# EthernetBoardPanel.net
KiCad netlist of a schematic drawn in EAGLE
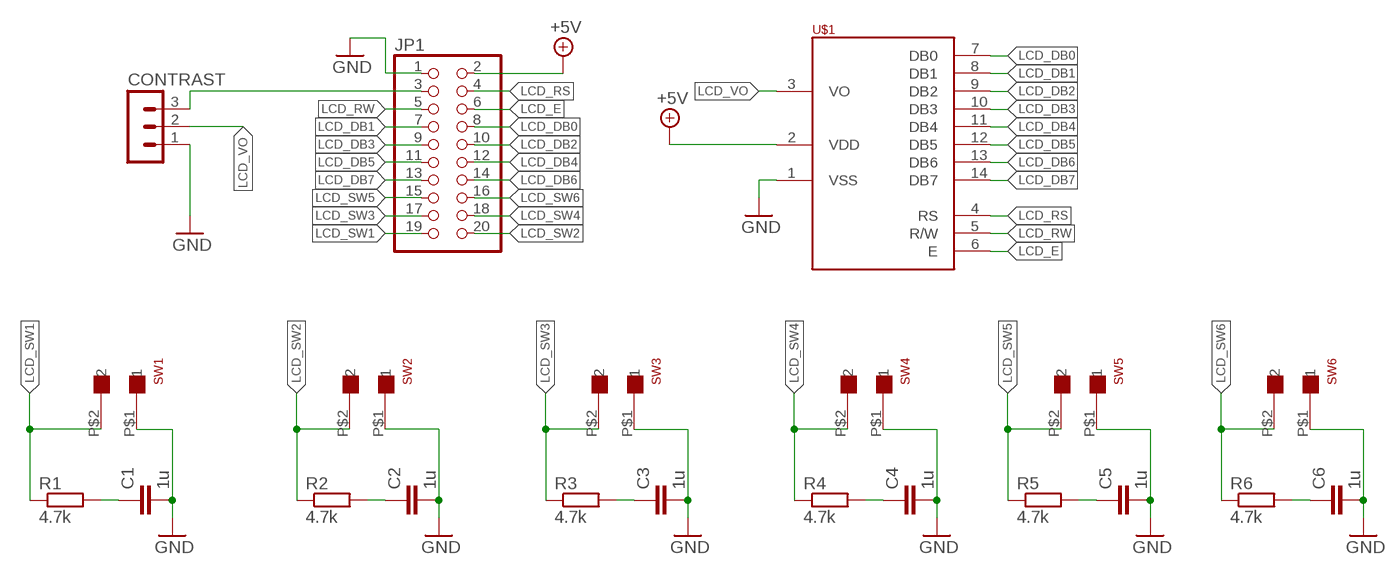
[diagram p0: schematic, sheet 1]

(export (version "E")
  (design (tool "Eeschema 10.0.6"))
  (components
    (comp (ref "C1")
      (value "1u")
      (footprint "eagle-import:C025-025X050")
      (libsource (lib "eagle-import") (part "C-EU025-025X050"))
    )
    (comp (ref "C2")
      (value "1u")
      (footprint "eagle-import:C025-025X050")
      (libsource (lib "eagle-import") (part "C-EU025-025X050"))
    )
    (comp (ref "C3")
      (value "1u")
      (footprint "eagle-import:C025-025X050")
      (libsource (lib "eagle-import") (part "C-EU025-025X050"))
    )
    (comp (ref "C4")
      (value "1u")
      (footprint "eagle-import:C025-025X050")
      (libsource (lib "eagle-import") (part "C-EU025-025X050"))
    )
    (comp (ref "C5")
      (value "1u")
      (footprint "eagle-import:C025-025X050")
      (libsource (lib "eagle-import") (part "C-EU025-025X050"))
    )
    (comp (ref "C6")
      (value "1u")
      (footprint "eagle-import:C025-025X050")
      (libsource (lib "eagle-import") (part "C-EU025-025X050"))
    )
    (comp (ref "CONTRAST")
      (value "MA03-1")
      (footprint "eagle-import:MA03-1")
      (libsource (lib "eagle-import") (part "MA03-1"))
    )
    (comp (ref "JP1")
      (value "PINHD-2X10")
      (footprint "eagle-import:2X10")
      (libsource (lib "eagle-import") (part "PINHD-2X10"))
    )
    (comp (ref "R1")
      (value "4.7k")
      (footprint "eagle-import:0204_7")
      (libsource (lib "eagle-import") (part "R-EU_0204/7"))
    )
    (comp (ref "R2")
      (value "4.7k")
      (footprint "eagle-import:0204_7")
      (libsource (lib "eagle-import") (part "R-EU_0204/7"))
    )
    (comp (ref "R3")
      (value "4.7k")
      (footprint "eagle-import:0204_7")
      (libsource (lib "eagle-import") (part "R-EU_0204/7"))
    )
    (comp (ref "R4")
      (value "4.7k")
      (footprint "eagle-import:0204_7")
      (libsource (lib "eagle-import") (part "R-EU_0204/7"))
    )
    (comp (ref "R5")
      (value "4.7k")
      (footprint "eagle-import:0204_7")
      (libsource (lib "eagle-import") (part "R-EU_0204/7"))
    )
    (comp (ref "R6")
      (value "4.7k")
      (footprint "eagle-import:0204_7")
      (libsource (lib "eagle-import") (part "R-EU_0204/7"))
    )
    (comp (ref "SW1")
      (value "XH-2")
      (footprint "eagle-import:XH-2")
      (libsource (lib "eagle-import") (part "XH-2"))
    )
    (comp (ref "SW2")
      (value "XH-2")
      (footprint "eagle-import:XH-2")
      (libsource (lib "eagle-import") (part "XH-2"))
    )
    (comp (ref "SW3")
      (value "XH-2")
      (footprint "eagle-import:XH-2")
      (libsource (lib "eagle-import") (part "XH-2"))
    )
    (comp (ref "SW4")
      (value "XH-2")
      (footprint "eagle-import:XH-2")
      (libsource (lib "eagle-import") (part "XH-2"))
    )
    (comp (ref "SW5")
      (value "XH-2")
      (footprint "eagle-import:XH-2")
      (libsource (lib "eagle-import") (part "XH-2"))
    )
    (comp (ref "SW6")
      (value "XH-2")
      (footprint "eagle-import:XH-2")
      (libsource (lib "eagle-import") (part "XH-2"))
    )
    (comp (ref "U$1")
      (value "SC2004")
      (footprint "eagle-import:SC2004")
      (libsource (lib "eagle-import") (part "SC2004"))
    )
  )
  (nets
    (net (code "1") (name "+5V") (class "Default")
      (node (ref "JP1") (pin "2") (pinfunction "2_2") (pintype "passive"))
      (node (ref "U$1") (pin "2") (pinfunction "VDD_2") (pintype "power_in"))
    )
    (net (code "2") (name "GND") (class "Default")
      (node (ref "C1") (pin "2") (pinfunction "2_2") (pintype "passive"))
      (node (ref "C2") (pin "2") (pinfunction "2_2") (pintype "passive"))
      (node (ref "C3") (pin "2") (pinfunction "2_2") (pintype "passive"))
      (node (ref "C4") (pin "2") (pinfunction "2_2") (pintype "passive"))
      (node (ref "C5") (pin "2") (pinfunction "2_2") (pintype "passive"))
      (node (ref "C6") (pin "2") (pinfunction "2_2") (pintype "passive"))
      (node (ref "CONTRAST") (pin "1") (pinfunction "1_1") (pintype "passive"))
      (node (ref "JP1") (pin "1") (pinfunction "1_1") (pintype "passive"))
      (node (ref "SW1") (pin "P$1") (pinfunction "1_P$1") (pintype "bidirectional"))
      (node (ref "SW2") (pin "P$1") (pinfunction "1_P$1") (pintype "bidirectional"))
      (node (ref "SW3") (pin "P$1") (pinfunction "1_P$1") (pintype "bidirectional"))
      (node (ref "SW4") (pin "P$1") (pinfunction "1_P$1") (pintype "bidirectional"))
      (node (ref "SW5") (pin "P$1") (pinfunction "1_P$1") (pintype "bidirectional"))
      (node (ref "SW6") (pin "P$1") (pinfunction "1_P$1") (pintype "bidirectional"))
      (node (ref "U$1") (pin "1") (pinfunction "VSS_1") (pintype "power_in"))
    )
    (net (code "3") (name "LCD_DB0") (class "Default")
      (node (ref "JP1") (pin "8") (pinfunction "8_8") (pintype "passive"))
      (node (ref "U$1") (pin "7") (pinfunction "DB0_7") (pintype "bidirectional"))
    )
    (net (code "4") (name "LCD_DB1") (class "Default")
      (node (ref "JP1") (pin "7") (pinfunction "7_7") (pintype "passive"))
      (node (ref "U$1") (pin "8") (pinfunction "DB1_8") (pintype "bidirectional"))
    )
    (net (code "5") (name "LCD_DB2") (class "Default")
      (node (ref "JP1") (pin "10") (pinfunction "10_10") (pintype "passive"))
      (node (ref "U$1") (pin "9") (pinfunction "DB2_9") (pintype "bidirectional"))
    )
    (net (code "6") (name "LCD_DB3") (class "Default")
      (node (ref "JP1") (pin "9") (pinfunction "9_9") (pintype "passive"))
      (node (ref "U$1") (pin "10") (pinfunction "DB3_10") (pintype "bidirectional"))
    )
    (net (code "7") (name "LCD_DB4") (class "Default")
      (node (ref "JP1") (pin "12") (pinfunction "12_12") (pintype "passive"))
      (node (ref "U$1") (pin "11") (pinfunction "DB4_11") (pintype "bidirectional"))
    )
    (net (code "8") (name "LCD_DB5") (class "Default")
      (node (ref "JP1") (pin "11") (pinfunction "11_11") (pintype "passive"))
      (node (ref "U$1") (pin "12") (pinfunction "DB5_12") (pintype "bidirectional"))
    )
    (net (code "9") (name "LCD_DB6") (class "Default")
      (node (ref "JP1") (pin "14") (pinfunction "14_14") (pintype "passive"))
      (node (ref "U$1") (pin "13") (pinfunction "DB6_13") (pintype "bidirectional"))
    )
    (net (code "10") (name "LCD_DB7") (class "Default")
      (node (ref "JP1") (pin "13") (pinfunction "13_13") (pintype "passive"))
      (node (ref "U$1") (pin "14") (pinfunction "DB7_14") (pintype "bidirectional"))
    )
    (net (code "11") (name "LCD_E") (class "Default")
      (node (ref "JP1") (pin "6") (pinfunction "6_6") (pintype "passive"))
      (node (ref "U$1") (pin "6") (pinfunction "E_6") (pintype "bidirectional"))
    )
    (net (code "12") (name "LCD_RS") (class "Default")
      (node (ref "JP1") (pin "4") (pinfunction "4_4") (pintype "passive"))
      (node (ref "U$1") (pin "4") (pinfunction "RS_4") (pintype "bidirectional"))
    )
    (net (code "13") (name "LCD_RW") (class "Default")
      (node (ref "JP1") (pin "5") (pinfunction "5_5") (pintype "passive"))
      (node (ref "U$1") (pin "5") (pinfunction "R/W_5") (pintype "bidirectional"))
    )
    (net (code "14") (name "LCD_SW1") (class "Default")
      (node (ref "JP1") (pin "19") (pinfunction "19_19") (pintype "passive"))
      (node (ref "R1") (pin "1") (pinfunction "1_1") (pintype "passive"))
      (node (ref "SW1") (pin "P$2") (pinfunction "2_P$2") (pintype "bidirectional"))
    )
    (net (code "15") (name "LCD_SW2") (class "Default")
      (node (ref "JP1") (pin "20") (pinfunction "20_20") (pintype "passive"))
      (node (ref "R2") (pin "1") (pinfunction "1_1") (pintype "passive"))
      (node (ref "SW2") (pin "P$2") (pinfunction "2_P$2") (pintype "bidirectional"))
    )
    (net (code "16") (name "LCD_SW3") (class "Default")
      (node (ref "JP1") (pin "17") (pinfunction "17_17") (pintype "passive"))
      (node (ref "R3") (pin "1") (pinfunction "1_1") (pintype "passive"))
      (node (ref "SW3") (pin "P$2") (pinfunction "2_P$2") (pintype "bidirectional"))
    )
    (net (code "17") (name "LCD_SW4") (class "Default")
      (node (ref "JP1") (pin "18") (pinfunction "18_18") (pintype "passive"))
      (node (ref "R4") (pin "1") (pinfunction "1_1") (pintype "passive"))
      (node (ref "SW4") (pin "P$2") (pinfunction "2_P$2") (pintype "bidirectional"))
    )
    (net (code "18") (name "LCD_SW5") (class "Default")
      (node (ref "JP1") (pin "15") (pinfunction "15_15") (pintype "passive"))
      (node (ref "R5") (pin "1") (pinfunction "1_1") (pintype "passive"))
      (node (ref "SW5") (pin "P$2") (pinfunction "2_P$2") (pintype "bidirectional"))
    )
    (net (code "19") (name "LCD_SW6") (class "Default")
      (node (ref "JP1") (pin "16") (pinfunction "16_16") (pintype "passive"))
      (node (ref "R6") (pin "1") (pinfunction "1_1") (pintype "passive"))
      (node (ref "SW6") (pin "P$2") (pinfunction "2_P$2") (pintype "bidirectional"))
    )
    (net (code "20") (name "LCD_VO") (class "Default")
      (node (ref "CONTRAST") (pin "2") (pinfunction "2_2") (pintype "passive"))
      (node (ref "U$1") (pin "3") (pinfunction "VO_3") (pintype "bidirectional"))
    )
    (net (code "21") (name "Net-(C1-Pad1)") (class "Default")
      (node (ref "C1") (pin "1") (pinfunction "1_1") (pintype "passive"))
      (node (ref "R1") (pin "2") (pinfunction "2_2") (pintype "passive"))
    )
    (net (code "22") (name "Net-(C2-Pad1)") (class "Default")
      (node (ref "C2") (pin "1") (pinfunction "1_1") (pintype "passive"))
      (node (ref "R2") (pin "2") (pinfunction "2_2") (pintype "passive"))
    )
    (net (code "23") (name "Net-(C3-Pad1)") (class "Default")
      (node (ref "C3") (pin "1") (pinfunction "1_1") (pintype "passive"))
      (node (ref "R3") (pin "2") (pinfunction "2_2") (pintype "passive"))
    )
    (net (code "24") (name "Net-(C4-Pad1)") (class "Default")
      (node (ref "C4") (pin "1") (pinfunction "1_1") (pintype "passive"))
      (node (ref "R4") (pin "2") (pinfunction "2_2") (pintype "passive"))
    )
    (net (code "25") (name "Net-(C5-Pad1)") (class "Default")
      (node (ref "C5") (pin "1") (pinfunction "1_1") (pintype "passive"))
      (node (ref "R5") (pin "2") (pinfunction "2_2") (pintype "passive"))
    )
    (net (code "26") (name "Net-(C6-Pad1)") (class "Default")
      (node (ref "C6") (pin "1") (pinfunction "1_1") (pintype "passive"))
      (node (ref "R6") (pin "2") (pinfunction "2_2") (pintype "passive"))
    )
    (net (code "27") (name "Net-(CONTRAST-Pad3)") (class "Default")
      (node (ref "CONTRAST") (pin "3") (pinfunction "3_3") (pintype "passive"))
      (node (ref "JP1") (pin "3") (pinfunction "3_3") (pintype "passive"))
    )
  )
)
